# PCFX_Mouse_rev_D.net
KiCad netlist of a schematic drawn in EAGLE
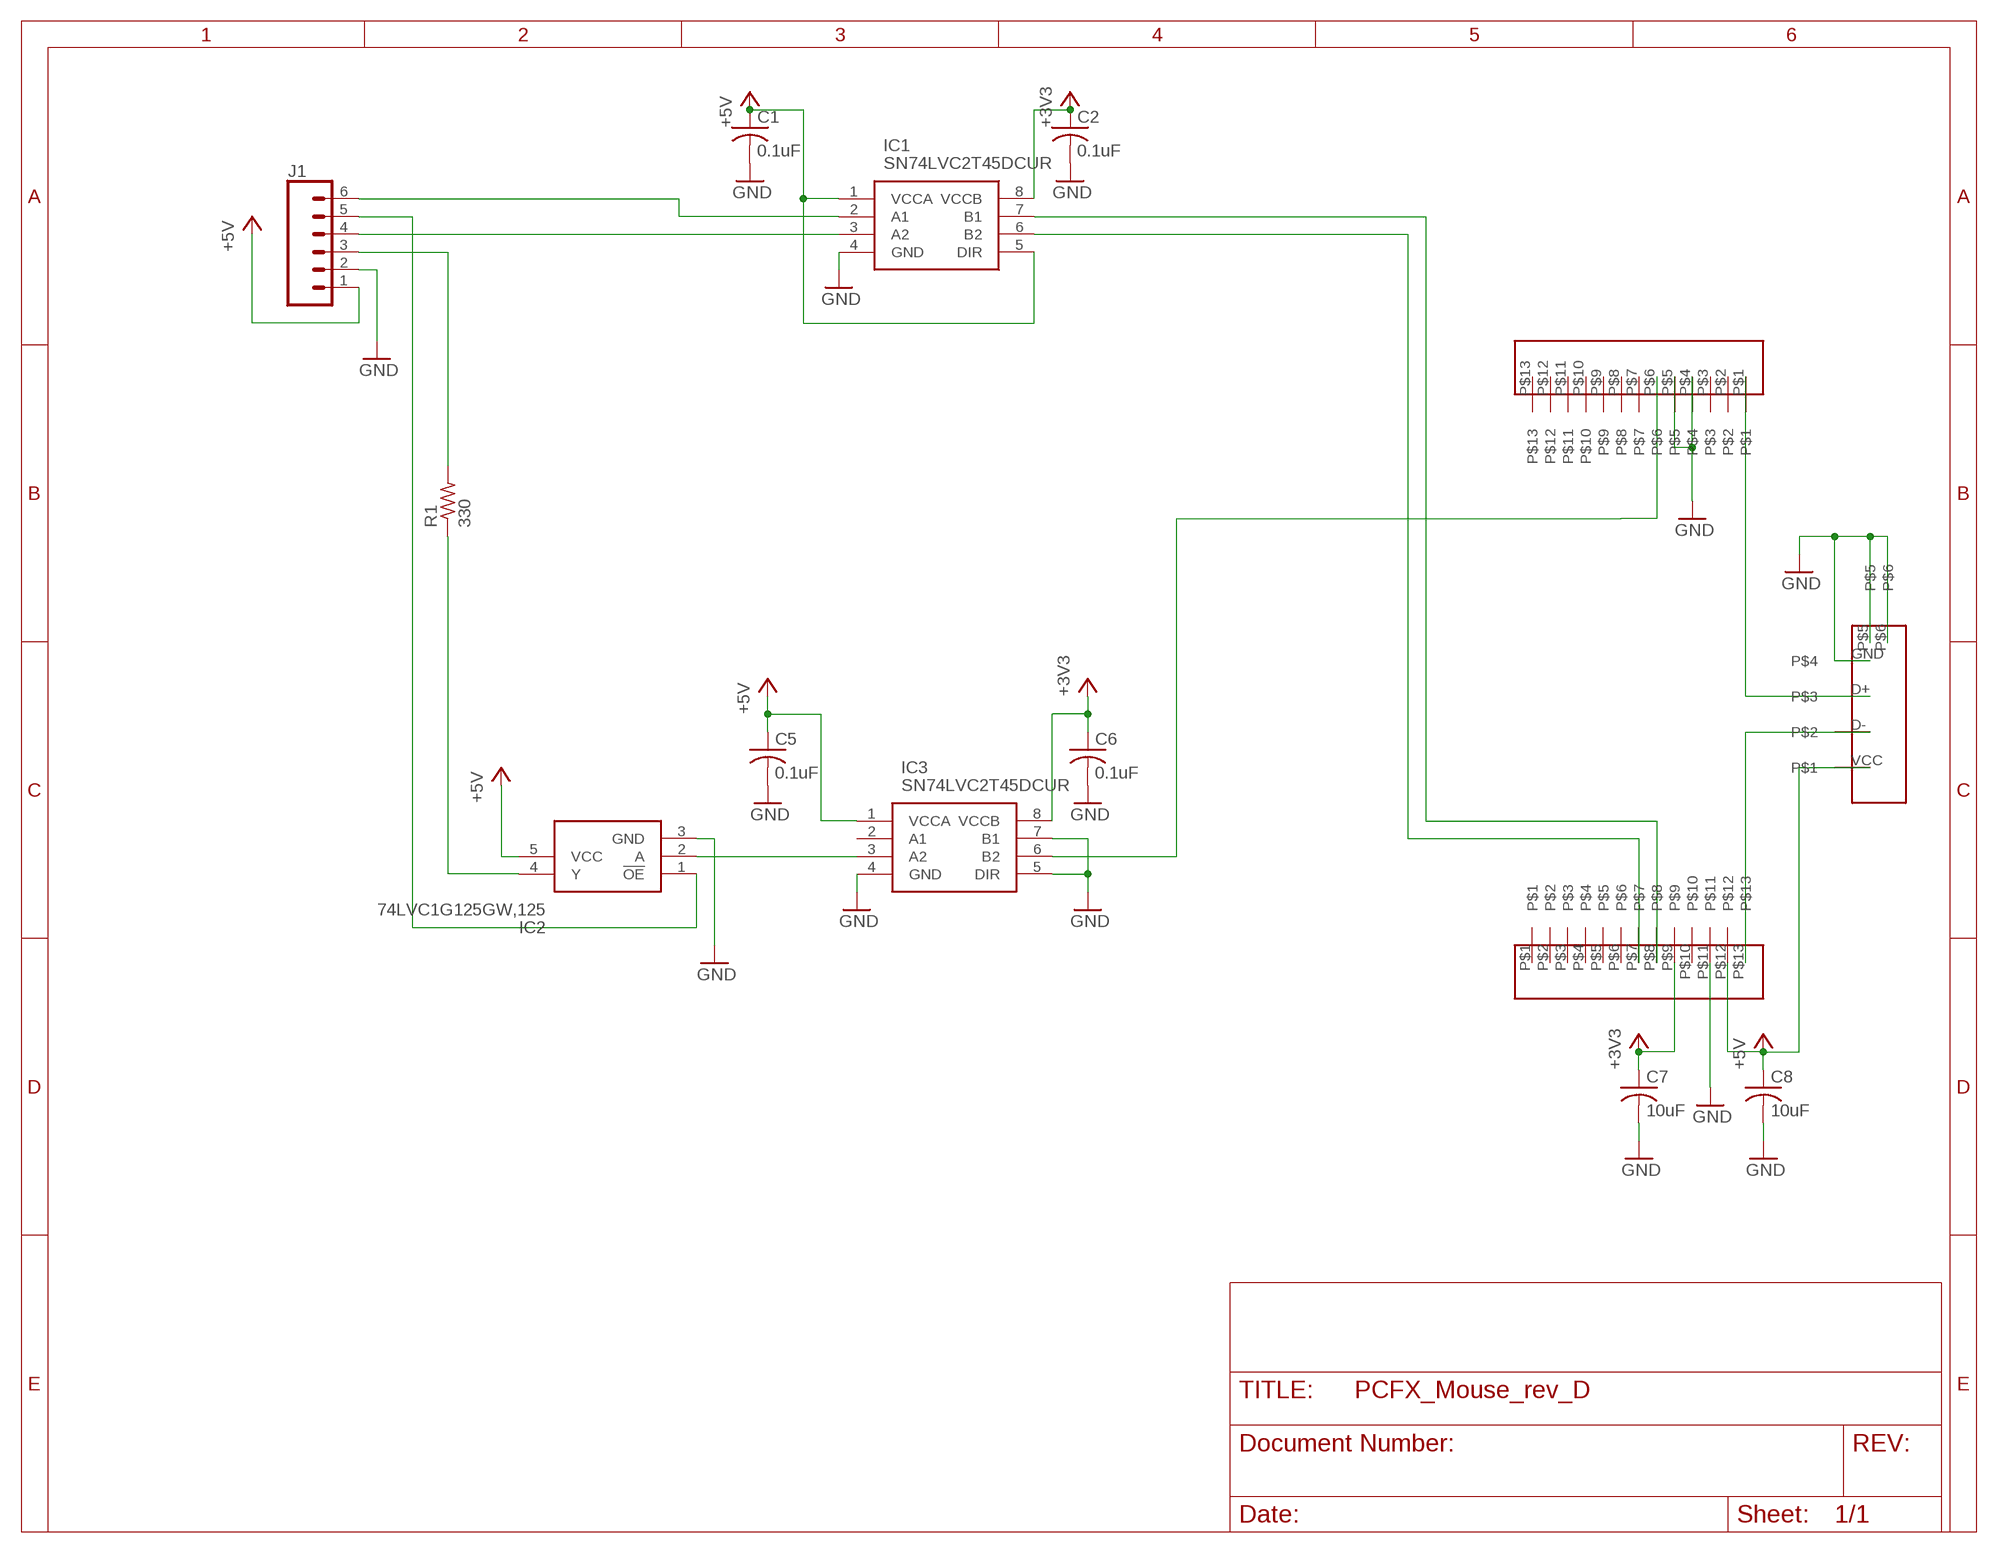
[diagram p0: schematic, sheet 1]

(export (version "E")
  (design (tool "Eeschema 10.0.6"))
  (components
    (comp (ref "C1")
      (value "0.1uF")
      (footprint "eagle-import:C0402")
      (libsource (lib "eagle-import") (part "C-USC0402"))
    )
    (comp (ref "C2")
      (value "0.1uF")
      (footprint "eagle-import:C0402")
      (libsource (lib "eagle-import") (part "C-USC0402"))
    )
    (comp (ref "C5")
      (value "0.1uF")
      (footprint "eagle-import:C0402")
      (libsource (lib "eagle-import") (part "C-USC0402"))
    )
    (comp (ref "C6")
      (value "0.1uF")
      (footprint "eagle-import:C0402")
      (libsource (lib "eagle-import") (part "C-USC0402"))
    )
    (comp (ref "C7")
      (value "10uF")
      (footprint "eagle-import:C0805")
      (libsource (lib "eagle-import") (part "resistor_348_C-USC0805"))
    )
    (comp (ref "C8")
      (value "10uF")
      (footprint "eagle-import:C0805")
      (libsource (lib "eagle-import") (part "resistor_348_C-USC0805"))
    )
    (comp (ref "IC1")
      (value "SN74LVC2T45DCUR")
      (footprint "eagle-import:SOP50P310X90-8N")
      (fields (field (name "MOUSER_PART_NUMBER") "595-SN74LVC2T45DCUR"))
      (libsource (lib "eagle-import") (part "SN74LVC2T45DCUR"))
    )
    (comp (ref "IC2")
      (value "74LVC1G125GW,125")
      (footprint "eagle-import:SOT65P212X110-5N")
      (fields (field (name "MOUSER_PART_NUMBER") "771-74LVC1G125GW-G"))
      (libsource (lib "eagle-import") (part "74LVC1G125GW,125"))
    )
    (comp (ref "IC3")
      (value "SN74LVC2T45DCUR")
      (footprint "eagle-import:SOP50P310X90-8N")
      (fields (field (name "MOUSER_PART_NUMBER") "595-SN74LVC2T45DCUR"))
      (libsource (lib "eagle-import") (part "SN74LVC2T45DCUR"))
    )
    (comp (ref "J1")
      (value "CONN_06NO_SILK_FEMALE_PTH")
      (footprint "eagle-import:1X06_NO_SILK")
      (libsource (lib "eagle-import") (part "CONN_06NO_SILK_FEMALE_PTH"))
    )
    (comp (ref "J2")
      (value "CONN_1X13")
      (footprint "eagle-import:CONN_1X13")
      (libsource (lib "eagle-import") (part "CONN_1X13"))
    )
    (comp (ref "J3")
      (value "CONN_1X13")
      (footprint "eagle-import:CONN_1X13")
      (libsource (lib "eagle-import") (part "CONN_1X13"))
    )
    (comp (ref "R1")
      (value "330")
      (footprint "eagle-import:R0402")
      (libsource (lib "eagle-import") (part "R-US_R0402"))
    )
    (comp (ref "U$1")
      (value "912-121A2026S10100")
      (footprint "eagle-import:912-121A2026S10100")
      (libsource (lib "eagle-import") (part "912-121A2026S10100"))
    )
  )
  (nets
    (net (code "1") (name "+3V3") (class "Default")
      (node (ref "C2") (pin "1") (pinfunction "1_1") (pintype "passive"))
      (node (ref "C6") (pin "1") (pinfunction "1_1") (pintype "passive"))
      (node (ref "C7") (pin "1") (pinfunction "1_1") (pintype "passive"))
      (node (ref "IC1") (pin "8") (pinfunction "VCCB_8") (pintype "bidirectional"))
      (node (ref "IC3") (pin "8") (pinfunction "VCCB_8") (pintype "bidirectional"))
      (node (ref "J2") (pin "P$9") (pinfunction "P$9_P$9") (pintype "bidirectional"))
    )
    (net (code "2") (name "+5V") (class "Default")
      (node (ref "C1") (pin "1") (pinfunction "1_1") (pintype "passive"))
      (node (ref "C5") (pin "1") (pinfunction "1_1") (pintype "passive"))
      (node (ref "C8") (pin "1") (pinfunction "1_1") (pintype "passive"))
      (node (ref "IC1") (pin "1") (pinfunction "VCCA_1") (pintype "bidirectional"))
      (node (ref "IC1") (pin "5") (pinfunction "DIR_5") (pintype "bidirectional"))
      (node (ref "IC2") (pin "5") (pinfunction "VCC_5") (pintype "bidirectional"))
      (node (ref "IC3") (pin "1") (pinfunction "VCCA_1") (pintype "bidirectional"))
      (node (ref "J1") (pin "1") (pinfunction "1_1") (pintype "passive"))
      (node (ref "J2") (pin "P$12") (pinfunction "P$12_P$12") (pintype "bidirectional"))
      (node (ref "U$1") (pin "VCC") (pinfunction "P$1_VCC") (pintype "bidirectional"))
    )
    (net (code "3") (name "GND") (class "Default")
      (node (ref "C1") (pin "2") (pinfunction "2_2") (pintype "passive"))
      (node (ref "C2") (pin "2") (pinfunction "2_2") (pintype "passive"))
      (node (ref "C5") (pin "2") (pinfunction "2_2") (pintype "passive"))
      (node (ref "C6") (pin "2") (pinfunction "2_2") (pintype "passive"))
      (node (ref "C7") (pin "2") (pinfunction "2_2") (pintype "passive"))
      (node (ref "C8") (pin "2") (pinfunction "2_2") (pintype "passive"))
      (node (ref "IC1") (pin "4") (pinfunction "GND_4") (pintype "bidirectional"))
      (node (ref "IC2") (pin "3") (pinfunction "GND_3") (pintype "bidirectional"))
      (node (ref "IC3") (pin "4") (pinfunction "GND_4") (pintype "bidirectional"))
      (node (ref "IC3") (pin "5") (pinfunction "DIR_5") (pintype "bidirectional"))
      (node (ref "IC3") (pin "7") (pinfunction "B1_7") (pintype "bidirectional"))
      (node (ref "J1") (pin "2") (pinfunction "2_2") (pintype "passive"))
      (node (ref "J2") (pin "P$11") (pinfunction "P$11_P$11") (pintype "bidirectional"))
      (node (ref "J3") (pin "P$4") (pinfunction "P$4_P$4") (pintype "bidirectional"))
      (node (ref "J3") (pin "P$5") (pinfunction "P$5_P$5") (pintype "bidirectional"))
      (node (ref "U$1") (pin "GND") (pinfunction "P$4_GND") (pintype "bidirectional"))
      (node (ref "U$1") (pin "P$5") (pinfunction "P$5_P$5") (pintype "bidirectional"))
      (node (ref "U$1") (pin "P$6") (pinfunction "P$6_P$6") (pintype "bidirectional"))
    )
    (net (code "4") (name "Net-(IC1-A1)") (class "Default")
      (node (ref "IC1") (pin "2") (pinfunction "A1_2") (pintype "bidirectional"))
      (node (ref "J1") (pin "6") (pinfunction "6_6") (pintype "passive"))
    )
    (net (code "5") (name "Net-(IC1-A2)") (class "Default")
      (node (ref "IC1") (pin "3") (pinfunction "A2_3") (pintype "bidirectional"))
      (node (ref "J1") (pin "4") (pinfunction "4_4") (pintype "passive"))
    )
    (net (code "6") (name "Net-(IC1-B1)") (class "Default")
      (node (ref "IC1") (pin "7") (pinfunction "B1_7") (pintype "bidirectional"))
      (node (ref "J2") (pin "P$8") (pinfunction "P$8_P$8") (pintype "bidirectional"))
    )
    (net (code "7") (name "Net-(IC1-B2)") (class "Default")
      (node (ref "IC1") (pin "6") (pinfunction "B2_6") (pintype "bidirectional"))
      (node (ref "J2") (pin "P$7") (pinfunction "P$7_P$7") (pintype "bidirectional"))
    )
    (net (code "8") (name "Net-(IC2-A)") (class "Default")
      (node (ref "IC2") (pin "2") (pinfunction "A_2") (pintype "bidirectional"))
      (node (ref "IC3") (pin "3") (pinfunction "A2_3") (pintype "bidirectional"))
    )
    (net (code "9") (name "Net-(IC2-Y)") (class "Default")
      (node (ref "IC2") (pin "4") (pinfunction "Y_4") (pintype "bidirectional"))
      (node (ref "R1") (pin "1") (pinfunction "1_1") (pintype "passive"))
    )
    (net (code "10") (name "Net-(IC2-~{OE})") (class "Default")
      (node (ref "IC2") (pin "1") (pinfunction "~{OE}_1") (pintype "bidirectional"))
      (node (ref "J1") (pin "5") (pinfunction "5_5") (pintype "passive"))
    )
    (net (code "11") (name "Net-(IC3-B2)") (class "Default")
      (node (ref "IC3") (pin "6") (pinfunction "B2_6") (pintype "bidirectional"))
      (node (ref "J3") (pin "P$6") (pinfunction "P$6_P$6") (pintype "bidirectional"))
    )
    (net (code "12") (name "Net-(J1-Pad3)") (class "Default")
      (node (ref "J1") (pin "3") (pinfunction "3_3") (pintype "passive"))
      (node (ref "R1") (pin "2") (pinfunction "2_2") (pintype "passive"))
    )
    (net (code "13") (name "Net-(U$1-P$2)") (class "Default")
      (node (ref "J2") (pin "P$13") (pinfunction "P$13_P$13") (pintype "bidirectional"))
      (node (ref "U$1") (pin "D-") (pinfunction "P$2_D-") (pintype "bidirectional"))
    )
    (net (code "14") (name "Net-(U$1-P$3)") (class "Default")
      (node (ref "J3") (pin "P$1") (pinfunction "P$1_P$1") (pintype "bidirectional"))
      (node (ref "U$1") (pin "D+") (pinfunction "P$3_D+") (pintype "bidirectional"))
    )
    (net (code "15") (name "unconnected-(IC3-A1-Pad2)") (class "Default")
      (node (ref "IC3") (pin "2") (pinfunction "A1_2") (pintype "bidirectional"))
    )
    (net (code "16") (name "unconnected-(J2-PadP$1)") (class "Default")
      (node (ref "J2") (pin "P$1") (pinfunction "P$1_P$1") (pintype "bidirectional"))
    )
    (net (code "17") (name "unconnected-(J2-PadP$2)") (class "Default")
      (node (ref "J2") (pin "P$2") (pinfunction "P$2_P$2") (pintype "bidirectional"))
    )
    (net (code "18") (name "unconnected-(J2-PadP$3)") (class "Default")
      (node (ref "J2") (pin "P$3") (pinfunction "P$3_P$3") (pintype "bidirectional"))
    )
    (net (code "19") (name "unconnected-(J2-PadP$4)") (class "Default")
      (node (ref "J2") (pin "P$4") (pinfunction "P$4_P$4") (pintype "bidirectional"))
    )
    (net (code "20") (name "unconnected-(J2-PadP$5)") (class "Default")
      (node (ref "J2") (pin "P$5") (pinfunction "P$5_P$5") (pintype "bidirectional"))
    )
    (net (code "21") (name "unconnected-(J2-PadP$6)") (class "Default")
      (node (ref "J2") (pin "P$6") (pinfunction "P$6_P$6") (pintype "bidirectional"))
    )
    (net (code "22") (name "unconnected-(J2-PadP$10)") (class "Default")
      (node (ref "J2") (pin "P$10") (pinfunction "P$10_P$10") (pintype "bidirectional"))
    )
    (net (code "23") (name "unconnected-(J3-PadP$2)") (class "Default")
      (node (ref "J3") (pin "P$2") (pinfunction "P$2_P$2") (pintype "bidirectional"))
    )
    (net (code "24") (name "unconnected-(J3-PadP$3)") (class "Default")
      (node (ref "J3") (pin "P$3") (pinfunction "P$3_P$3") (pintype "bidirectional"))
    )
    (net (code "25") (name "unconnected-(J3-PadP$7)") (class "Default")
      (node (ref "J3") (pin "P$7") (pinfunction "P$7_P$7") (pintype "bidirectional"))
    )
    (net (code "26") (name "unconnected-(J3-PadP$8)") (class "Default")
      (node (ref "J3") (pin "P$8") (pinfunction "P$8_P$8") (pintype "bidirectional"))
    )
    (net (code "27") (name "unconnected-(J3-PadP$9)") (class "Default")
      (node (ref "J3") (pin "P$9") (pinfunction "P$9_P$9") (pintype "bidirectional"))
    )
    (net (code "28") (name "unconnected-(J3-PadP$10)") (class "Default")
      (node (ref "J3") (pin "P$10") (pinfunction "P$10_P$10") (pintype "bidirectional"))
    )
    (net (code "29") (name "unconnected-(J3-PadP$11)") (class "Default")
      (node (ref "J3") (pin "P$11") (pinfunction "P$11_P$11") (pintype "bidirectional"))
    )
    (net (code "30") (name "unconnected-(J3-PadP$12)") (class "Default")
      (node (ref "J3") (pin "P$12") (pinfunction "P$12_P$12") (pintype "bidirectional"))
    )
    (net (code "31") (name "unconnected-(J3-PadP$13)") (class "Default")
      (node (ref "J3") (pin "P$13") (pinfunction "P$13_P$13") (pintype "bidirectional"))
    )
  )
)
